# BreaV6B.net
KiCad netlist of a schematic drawn in EAGLE
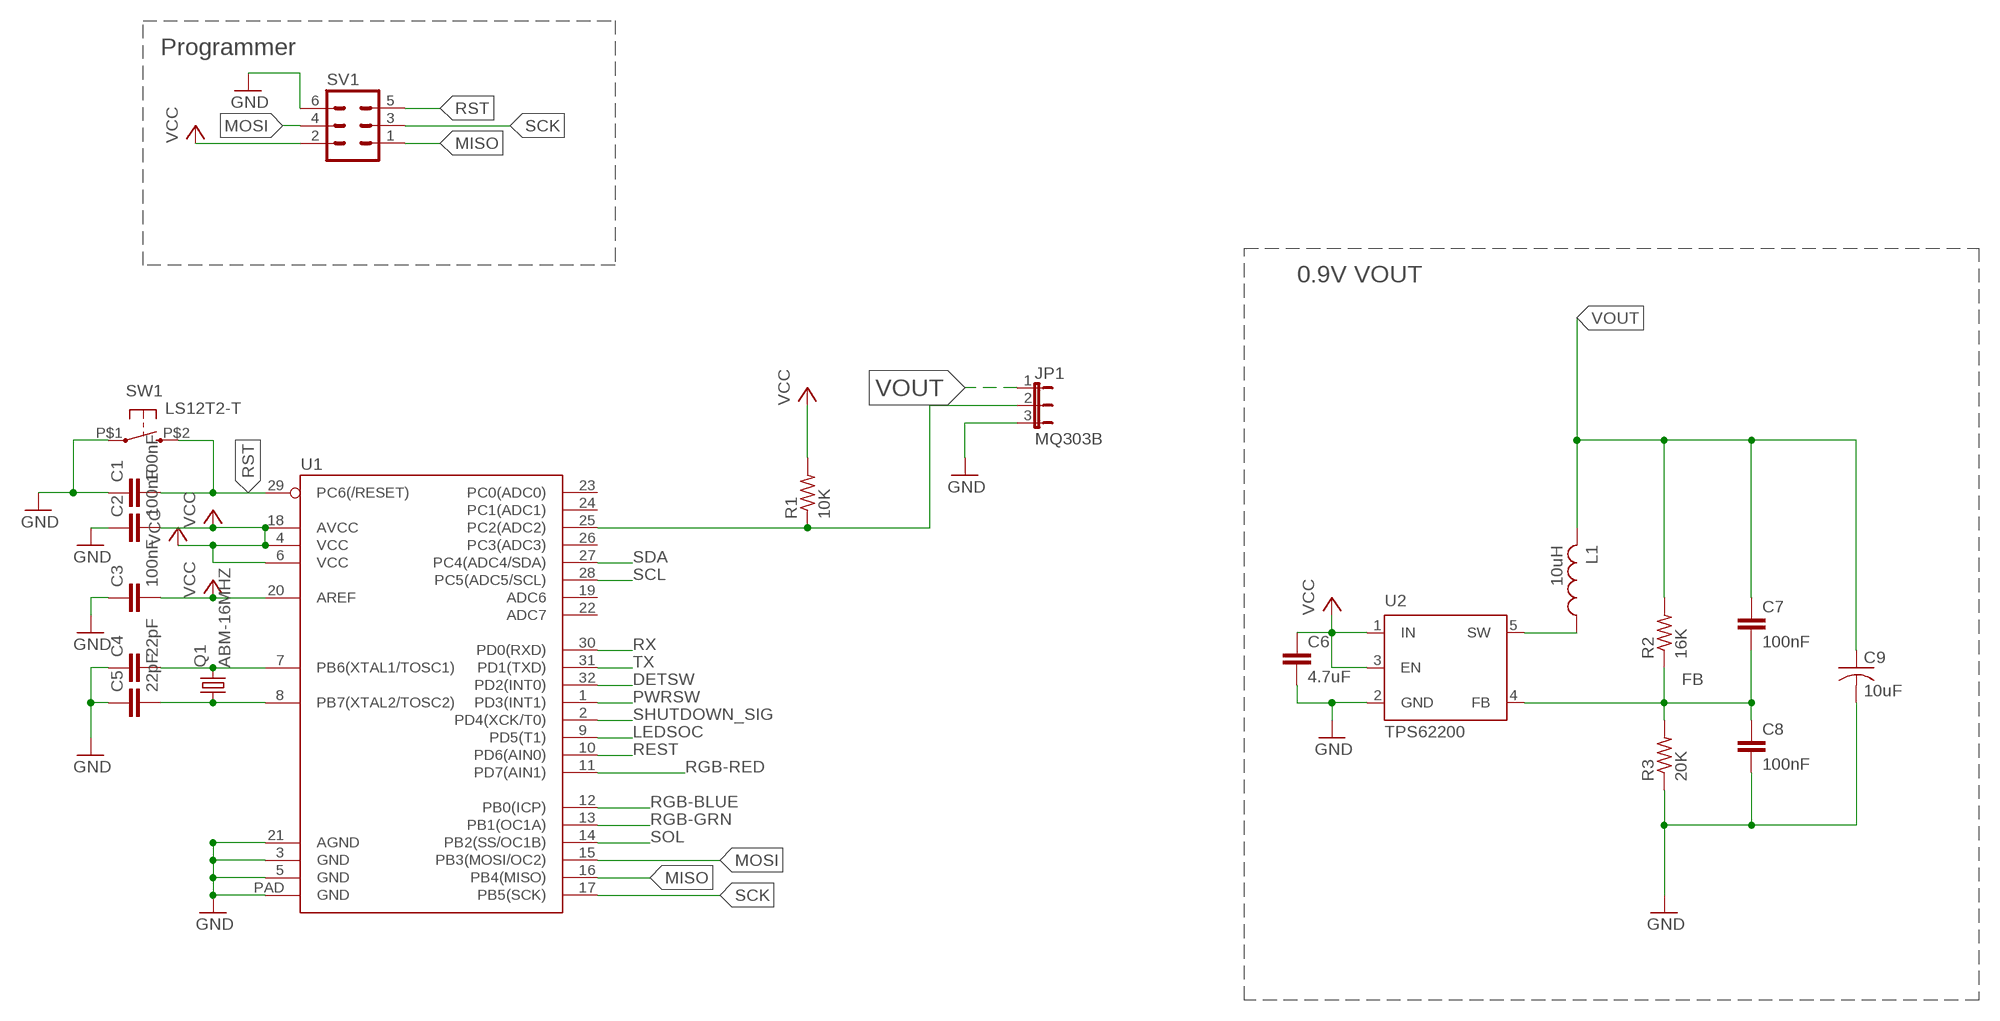
[diagram p0: schematic, sheet 1]
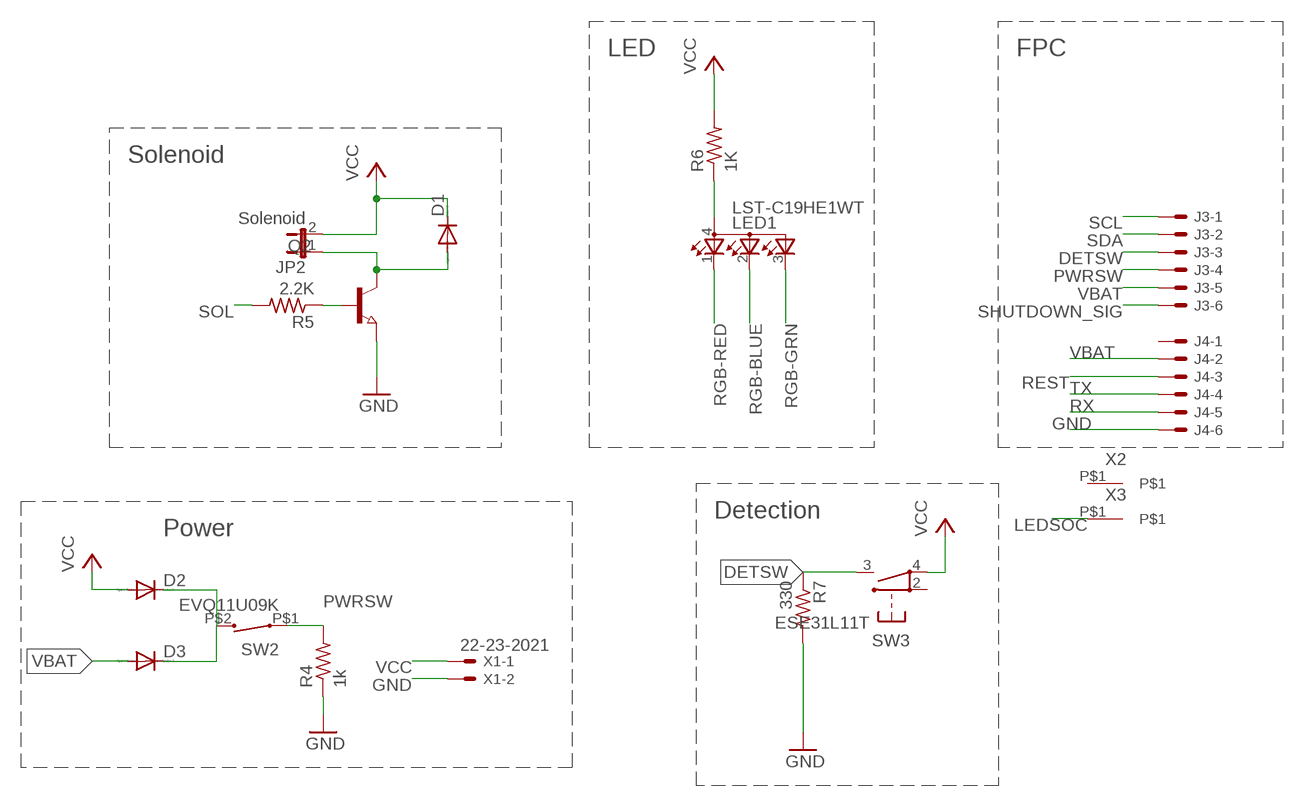
[diagram p1: schematic, sheet 2]

(export (version "E")
  (design (tool "Eeschema 10.0.6"))
  (components
    (comp (ref "D1")
      (value "DIODE-SOD123")
      (footprint "eagle-import:SOD123")
      (libsource (lib "eagle-import") (part "DIODE-SOD123"))
    )
    (comp (ref "D2")
      (value "DIODE-SOD523")
      (footprint "eagle-import:SOD523")
      (libsource (lib "eagle-import") (part "diode_210_DIODE-SOD523"))
    )
    (comp (ref "D3")
      (value "DIODE-SOD523")
      (footprint "eagle-import:SOD523")
      (libsource (lib "eagle-import") (part "diode_210_DIODE-SOD523"))
    )
    (comp (ref "J3")
      (value "XF2L-0635-1")
      (footprint "eagle-import:XF2L-0635-1")
      (libsource (lib "eagle-import") (part "XF2-06?35-1L"))
    )
    (comp (ref "J4")
      (value "XF2L-0625-1")
      (footprint "eagle-import:XF2L-0625-1")
      (fields (field (name "MF") "OMRON COMPONENTS USA"))
      (libsource (lib "eagle-import") (part "XF2-06?25-1L"))
    )
    (comp (ref "JP2")
      (value "Solenoid")
      (footprint "eagle-import:JP1")
      (libsource (lib "eagle-import") (part "JP1E"))
    )
    (comp (ref "LED1")
      (value "LST-C19HE1WT")
      (footprint "eagle-import:LST-C19HE1WT")
      (libsource (lib "eagle-import") (part "LST-C19HE1WT"))
    )
    (comp (ref "Q2")
      (value "NPN-TRANSISTOR_SOT23")
      (footprint "eagle-import:SOT23")
      (libsource (lib "eagle-import") (part "NPN-TRANSISTOR_SOT23"))
    )
    (comp (ref "R4")
      (value "1k")
      (footprint "eagle-import:R0402")
      (libsource (lib "eagle-import") (part "R-US_R0402"))
    )
    (comp (ref "R5")
      (value "2.2K")
      (footprint "eagle-import:R0402")
      (libsource (lib "eagle-import") (part "R-US_R0402"))
    )
    (comp (ref "R6")
      (value "1K")
      (footprint "eagle-import:R0402")
      (libsource (lib "eagle-import") (part "R-US_R0402"))
    )
    (comp (ref "R7")
      (value "330")
      (footprint "eagle-import:R0402")
      (libsource (lib "eagle-import") (part "R-US_R0402"))
    )
    (comp (ref "SW2")
      (value "EVQ11U09K")
      (footprint "eagle-import:EVQ11U-09K")
      (libsource (lib "eagle-import") (part "EVQ11U09K"))
    )
    (comp (ref "SW3")
      (value "ESE31L11T")
      (footprint "eagle-import:SWITCH")
      (libsource (lib "eagle-import") (part "ESE31L11T"))
    )
    (comp (ref "X1")
      (value "22-23-2021")
      (footprint "eagle-import:22-23-2021")
      (fields (field (name "MF") "MOLEX"))
      (libsource (lib "eagle-import") (part "22-23-2021"))
    )
    (comp (ref "X2")
      (value "CON-1PIN")
      (footprint "eagle-import:CON-1PIN")
      (libsource (lib "eagle-import") (part "CON-1PIN"))
    )
    (comp (ref "X3")
      (value "CON-1PINB")
      (footprint "eagle-import:CON-1PIN-B")
      (libsource (lib "eagle-import") (part "CON-1PINB"))
    )
    (comp (ref "C1")
      (value "100nF")
      (footprint "eagle-import:C0603")
      (libsource (lib "eagle-import") (part "C-EUC0603"))
    )
    (comp (ref "C2")
      (value "100nF")
      (footprint "eagle-import:C0603")
      (libsource (lib "eagle-import") (part "C-EUC0603"))
    )
    (comp (ref "C3")
      (value "100nF")
      (footprint "eagle-import:C0603")
      (libsource (lib "eagle-import") (part "C-EUC0603"))
    )
    (comp (ref "C4")
      (value "22pF")
      (footprint "eagle-import:C0603")
      (libsource (lib "eagle-import") (part "C-EUC0603"))
    )
    (comp (ref "C5")
      (value "22pF")
      (footprint "eagle-import:C0603")
      (libsource (lib "eagle-import") (part "C-EUC0603"))
    )
    (comp (ref "C6")
      (value "4.7uF")
      (footprint "eagle-import:C0402")
      (libsource (lib "eagle-import") (part "C-EUC0402"))
    )
    (comp (ref "C7")
      (value "100nF")
      (footprint "eagle-import:C0402")
      (libsource (lib "eagle-import") (part "C-EUC0402"))
    )
    (comp (ref "C8")
      (value "100nF")
      (footprint "eagle-import:C0402")
      (libsource (lib "eagle-import") (part "C-EUC0402"))
    )
    (comp (ref "C9")
      (value "10uF")
      (footprint "eagle-import:C0805K")
      (libsource (lib "eagle-import") (part "C-USC0805K"))
    )
    (comp (ref "JP1")
      (value "MQ303B")
      (footprint "eagle-import:JP2")
      (libsource (lib "eagle-import") (part "JP2E"))
    )
    (comp (ref "L1")
      (value "10uH")
      (footprint "eagle-import:L2825P")
      (libsource (lib "eagle-import") (part "L-USL2825P"))
    )
    (comp (ref "Q1")
      (value "ABM-16MHZ")
      (footprint "eagle-import:ABM-16MHZ")
      (libsource (lib "eagle-import") (part "ABM-16MHZ"))
    )
    (comp (ref "R1")
      (value "10K")
      (footprint "eagle-import:R0402")
      (libsource (lib "eagle-import") (part "R-US_R0402"))
    )
    (comp (ref "R2")
      (value "16K")
      (footprint "eagle-import:R0402")
      (libsource (lib "eagle-import") (part "R-US_R0402"))
    )
    (comp (ref "R3")
      (value "20K")
      (footprint "eagle-import:R0402")
      (libsource (lib "eagle-import") (part "R-US_R0402"))
    )
    (comp (ref "SV1")
      (value "MA03-2")
      (footprint "eagle-import:MA03-2")
      (libsource (lib "eagle-import") (part "MA03-2"))
    )
    (comp (ref "SW1")
      (value "LS12T2-T")
      (footprint "eagle-import:LS12T2-T")
      (libsource (lib "eagle-import") (part "LS12T2-T"))
    )
    (comp (ref "U1")
      (value "ATMEGA328P_MLFMLF32")
      (footprint "eagle-import:MLF32-PAD")
      (libsource (lib "eagle-import") (part "ATMEGA328P_MLFMLF32"))
    )
    (comp (ref "U2")
      (value "TPS62200")
      (footprint "eagle-import:TPS62200")
      (libsource (lib "eagle-import") (part "TPS62200"))
    )
  )
  (nets
    (net (code "1") (name "DETSW") (class "Default")
      (node (ref "J3") (pin "3") (pinfunction "MS_3") (pintype "passive"))
      (node (ref "R7") (pin "1") (pinfunction "1_1") (pintype "passive"))
      (node (ref "SW3") (pin "3") (pinfunction "1_3") (pintype "passive"))
      (node (ref "U1") (pin "32") (pinfunction "PD2(INT0)_32") (pintype "bidirectional"))
    )
    (net (code "2") (name "FB") (class "Default")
      (node (ref "C7") (pin "2") (pinfunction "2_2") (pintype "passive"))
      (node (ref "C8") (pin "1") (pinfunction "1_1") (pintype "passive"))
      (node (ref "R2") (pin "1") (pinfunction "1_1") (pintype "passive"))
      (node (ref "R3") (pin "2") (pinfunction "2_2") (pintype "passive"))
      (node (ref "U2") (pin "4") (pinfunction "FB_4") (pintype "passive"))
    )
    (net (code "3") (name "GND") (class "Default")
      (node (ref "C1") (pin "1") (pinfunction "1_1") (pintype "passive"))
      (node (ref "C2") (pin "1") (pinfunction "1_1") (pintype "passive"))
      (node (ref "C3") (pin "1") (pinfunction "1_1") (pintype "passive"))
      (node (ref "C4") (pin "1") (pinfunction "1_1") (pintype "passive"))
      (node (ref "C5") (pin "1") (pinfunction "1_1") (pintype "passive"))
      (node (ref "C6") (pin "2") (pinfunction "2_2") (pintype "passive"))
      (node (ref "C8") (pin "2") (pinfunction "2_2") (pintype "passive"))
      (node (ref "C9") (pin "2") (pinfunction "2_2") (pintype "passive"))
      (node (ref "J4") (pin "6") (pinfunction "MS_6") (pintype "passive"))
      (node (ref "JP1") (pin "3") (pinfunction "3_3") (pintype "passive"))
      (node (ref "Q2") (pin "2") (pinfunction "E_2") (pintype "passive"))
      (node (ref "R3") (pin "1") (pinfunction "1_1") (pintype "passive"))
      (node (ref "R4") (pin "1") (pinfunction "1_1") (pintype "passive"))
      (node (ref "R7") (pin "2") (pinfunction "2_2") (pintype "passive"))
      (node (ref "SV1") (pin "6") (pinfunction "MISO_6") (pintype "passive"))
      (node (ref "SW1") (pin "P$1") (pinfunction "S1_P$1") (pintype "passive"))
      (node (ref "U1") (pin "21") (pinfunction "AGND_21") (pintype "bidirectional"))
      (node (ref "U1") (pin "3") (pinfunction "GND_3") (pintype "bidirectional"))
      (node (ref "U1") (pin "5") (pinfunction "GND_5") (pintype "bidirectional"))
      (node (ref "U1") (pin "PAD") (pinfunction "GND_PAD") (pintype "bidirectional"))
      (node (ref "U2") (pin "2") (pinfunction "GND_2") (pintype "power_in"))
      (node (ref "X1") (pin "2") (pinfunction "S_2") (pintype "passive"))
    )
    (net (code "4") (name "LEDSOC") (class "Default")
      (node (ref "U1") (pin "9") (pinfunction "PD5(T1)_9") (pintype "bidirectional"))
      (node (ref "X3") (pin "P$1") (pinfunction "P$1_P$1") (pintype "bidirectional"))
    )
    (net (code "5") (name "MISO") (class "Default")
      (node (ref "SV1") (pin "1") (pinfunction "1_1") (pintype "passive"))
      (node (ref "U1") (pin "16") (pinfunction "PB4(MISO)_16") (pintype "bidirectional"))
    )
    (net (code "6") (name "MOSI") (class "Default")
      (node (ref "SV1") (pin "4") (pinfunction "4_4") (pintype "passive"))
      (node (ref "U1") (pin "15") (pinfunction "PB3(MOSI/OC2)_15") (pintype "bidirectional"))
    )
    (net (code "7") (name "Net-(LED1-A)") (class "Default")
      (node (ref "LED1") (pin "4") (pinfunction "A_4") (pintype "passive"))
      (node (ref "R6") (pin "1") (pinfunction "1_1") (pintype "passive"))
    )
    (net (code "8") (name "Net-(Q1-1)") (class "Default")
      (node (ref "C5") (pin "2") (pinfunction "2_2") (pintype "passive"))
      (node (ref "Q1") (pin "P$1") (pinfunction "1_P$1") (pintype "passive"))
      (node (ref "U1") (pin "8") (pinfunction "PB7(XTAL2/TOSC2)_8") (pintype "bidirectional"))
    )
    (net (code "9") (name "Net-(Q1-2)") (class "Default")
      (node (ref "C4") (pin "2") (pinfunction "2_2") (pintype "passive"))
      (node (ref "Q1") (pin "P$2") (pinfunction "2_P$2") (pintype "passive"))
      (node (ref "U1") (pin "7") (pinfunction "PB6(XTAL1/TOSC1)_7") (pintype "bidirectional"))
    )
    (net (code "10") (name "Net-(Q2-B)") (class "Default")
      (node (ref "Q2") (pin "1") (pinfunction "B_1") (pintype "passive"))
      (node (ref "R5") (pin "1") (pinfunction "1_1") (pintype "passive"))
    )
    (net (code "11") (name "Net-(Q2-C)") (class "Default")
      (node (ref "D1") (pin "A") (pinfunction "A_A") (pintype "passive"))
      (node (ref "JP2") (pin "1") (pinfunction "1_1") (pintype "passive"))
      (node (ref "Q2") (pin "3") (pinfunction "C_3") (pintype "passive"))
    )
    (net (code "12") (name "Net-(SW2-2)") (class "Default")
      (node (ref "D2") (pin "C") (pinfunction "C_C") (pintype "passive"))
      (node (ref "D3") (pin "C") (pinfunction "C_C") (pintype "passive"))
      (node (ref "SW2") (pin "P$2") (pinfunction "2_P$2") (pintype "passive"))
    )
    (net (code "13") (name "Net-(U1-PC2(ADC2))") (class "Default")
      (node (ref "JP1") (pin "2") (pinfunction "2_2") (pintype "passive"))
      (node (ref "R1") (pin "1") (pinfunction "1_1") (pintype "passive"))
      (node (ref "U1") (pin "25") (pinfunction "PC2(ADC2)_25") (pintype "bidirectional"))
    )
    (net (code "14") (name "Net-(U2-SW)") (class "Default")
      (node (ref "L1") (pin "1") (pinfunction "1_1") (pintype "passive"))
      (node (ref "U2") (pin "5") (pinfunction "SW_5") (pintype "passive"))
    )
    (net (code "15") (name "PWRSW") (class "Default")
      (node (ref "J3") (pin "4") (pinfunction "MS_4") (pintype "passive"))
      (node (ref "R4") (pin "2") (pinfunction "2_2") (pintype "passive"))
      (node (ref "SW2") (pin "P$1") (pinfunction "1_P$1") (pintype "passive"))
      (node (ref "U1") (pin "1") (pinfunction "PD3(INT1)_1") (pintype "bidirectional"))
    )
    (net (code "16") (name "REST") (class "Default")
      (node (ref "J4") (pin "3") (pinfunction "MS_3") (pintype "passive"))
      (node (ref "U1") (pin "10") (pinfunction "PD6(AIN0)_10") (pintype "bidirectional"))
    )
    (net (code "17") (name "RGB-BLUE") (class "Default")
      (node (ref "LED1") (pin "2") (pinfunction "CGREEN_2") (pintype "passive"))
      (node (ref "U1") (pin "12") (pinfunction "PB0(ICP)_12") (pintype "bidirectional"))
    )
    (net (code "18") (name "RGB-GRN") (class "Default")
      (node (ref "LED1") (pin "3") (pinfunction "CBLUE_3") (pintype "passive"))
      (node (ref "U1") (pin "13") (pinfunction "PB1(OC1A)_13") (pintype "bidirectional"))
    )
    (net (code "19") (name "RGB-RED") (class "Default")
      (node (ref "LED1") (pin "1") (pinfunction "CRED_1") (pintype "passive"))
      (node (ref "U1") (pin "11") (pinfunction "PD7(AIN1)_11") (pintype "bidirectional"))
    )
    (net (code "20") (name "RST") (class "Default")
      (node (ref "C1") (pin "2") (pinfunction "2_2") (pintype "passive"))
      (node (ref "SV1") (pin "5") (pinfunction "VTG_5") (pintype "passive"))
      (node (ref "SW1") (pin "P$2") (pinfunction "S2_P$2") (pintype "passive"))
      (node (ref "U1") (pin "29") (pinfunction "PC6(/RESET)_29") (pintype "bidirectional"))
    )
    (net (code "21") (name "RX") (class "Default")
      (node (ref "J4") (pin "5") (pinfunction "MS_5") (pintype "passive"))
      (node (ref "U1") (pin "30") (pinfunction "PD0(RXD)_30") (pintype "bidirectional"))
    )
    (net (code "22") (name "SCK") (class "Default")
      (node (ref "SV1") (pin "3") (pinfunction "3_3") (pintype "passive"))
      (node (ref "U1") (pin "17") (pinfunction "PB5(SCK)_17") (pintype "bidirectional"))
    )
    (net (code "23") (name "SCL") (class "Default")
      (node (ref "J3") (pin "1") (pinfunction "MS_1") (pintype "passive"))
      (node (ref "U1") (pin "28") (pinfunction "PC5(ADC5/SCL)_28") (pintype "bidirectional"))
    )
    (net (code "24") (name "SDA") (class "Default")
      (node (ref "J3") (pin "2") (pinfunction "MS_2") (pintype "passive"))
      (node (ref "U1") (pin "27") (pinfunction "PC4(ADC4/SDA)_27") (pintype "bidirectional"))
    )
    (net (code "25") (name "SHUTDOWN_SIG") (class "Default")
      (node (ref "J3") (pin "6") (pinfunction "MS_6") (pintype "passive"))
      (node (ref "U1") (pin "2") (pinfunction "PD4(XCK/T0)_2") (pintype "bidirectional"))
    )
    (net (code "26") (name "SOL") (class "Default")
      (node (ref "R5") (pin "2") (pinfunction "2_2") (pintype "passive"))
      (node (ref "U1") (pin "14") (pinfunction "PB2(SS/OC1B)_14") (pintype "bidirectional"))
    )
    (net (code "27") (name "TX") (class "Default")
      (node (ref "J4") (pin "4") (pinfunction "MS_4") (pintype "passive"))
      (node (ref "U1") (pin "31") (pinfunction "PD1(TXD)_31") (pintype "bidirectional"))
    )
    (net (code "28") (name "VBAT") (class "Default")
      (node (ref "D3") (pin "A") (pinfunction "A_A") (pintype "passive"))
      (node (ref "J3") (pin "5") (pinfunction "MS_5") (pintype "passive"))
      (node (ref "J4") (pin "2") (pinfunction "MS_2") (pintype "passive"))
    )
    (net (code "29") (name "VCC") (class "Default")
      (node (ref "C2") (pin "2") (pinfunction "2_2") (pintype "passive"))
      (node (ref "C3") (pin "2") (pinfunction "2_2") (pintype "passive"))
      (node (ref "C6") (pin "1") (pinfunction "1_1") (pintype "passive"))
      (node (ref "D1") (pin "C") (pinfunction "C_C") (pintype "passive"))
      (node (ref "D2") (pin "A") (pinfunction "A_A") (pintype "passive"))
      (node (ref "JP2") (pin "2") (pinfunction "2_2") (pintype "passive"))
      (node (ref "R1") (pin "2") (pinfunction "2_2") (pintype "passive"))
      (node (ref "R6") (pin "2") (pinfunction "2_2") (pintype "passive"))
      (node (ref "SV1") (pin "2") (pinfunction "2_2") (pintype "passive"))
      (node (ref "SW3") (pin "4") (pinfunction "C3_4") (pintype "passive"))
      (node (ref "U1") (pin "18") (pinfunction "AVCC_18") (pintype "bidirectional"))
      (node (ref "U1") (pin "20") (pinfunction "AREF_20") (pintype "bidirectional"))
      (node (ref "U1") (pin "4") (pinfunction "VCC_4") (pintype "bidirectional"))
      (node (ref "U1") (pin "6") (pinfunction "VCC_6") (pintype "bidirectional"))
      (node (ref "U2") (pin "1") (pinfunction "IN_1") (pintype "input"))
      (node (ref "U2") (pin "3") (pinfunction "EN_3") (pintype "input"))
      (node (ref "X1") (pin "1") (pinfunction "S_1") (pintype "passive"))
    )
    (net (code "30") (name "VOUT") (class "Default")
      (node (ref "C7") (pin "1") (pinfunction "1_1") (pintype "passive"))
      (node (ref "C9") (pin "1") (pinfunction "1_1") (pintype "passive"))
      (node (ref "JP1") (pin "1") (pinfunction "1_1") (pintype "passive"))
      (node (ref "L1") (pin "2") (pinfunction "2_2") (pintype "passive"))
      (node (ref "R2") (pin "2") (pinfunction "2_2") (pintype "passive"))
    )
    (net (code "31") (name "unconnected-(J4A-MS-Pad1)") (class "Default")
      (node (ref "J4") (pin "1") (pinfunction "MS_1") (pintype "passive"))
    )
    (net (code "32") (name "unconnected-(SW3-C2-Pad2)") (class "Default")
      (node (ref "SW3") (pin "2") (pinfunction "C2_2") (pintype "passive"))
    )
    (net (code "33") (name "unconnected-(U1-ADC6-Pad19)") (class "Default")
      (node (ref "U1") (pin "19") (pinfunction "ADC6_19") (pintype "bidirectional"))
    )
    (net (code "34") (name "unconnected-(U1-ADC7-Pad22)") (class "Default")
      (node (ref "U1") (pin "22") (pinfunction "ADC7_22") (pintype "bidirectional"))
    )
    (net (code "35") (name "unconnected-(U1-PC0(ADC0)-Pad23)") (class "Default")
      (node (ref "U1") (pin "23") (pinfunction "PC0(ADC0)_23") (pintype "bidirectional"))
    )
    (net (code "36") (name "unconnected-(U1-PC1(ADC1)-Pad24)") (class "Default")
      (node (ref "U1") (pin "24") (pinfunction "PC1(ADC1)_24") (pintype "bidirectional"))
    )
    (net (code "37") (name "unconnected-(U1-PC3(ADC3)-Pad26)") (class "Default")
      (node (ref "U1") (pin "26") (pinfunction "PC3(ADC3)_26") (pintype "bidirectional"))
    )
    (net (code "38") (name "unconnected-(X2-PadP$1)") (class "Default")
      (node (ref "X2") (pin "P$1") (pinfunction "P$1_P$1") (pintype "bidirectional"))
    )
  )
)
